# PAGE3.net
KiCad netlist of a schematic drawn in Altium Designer
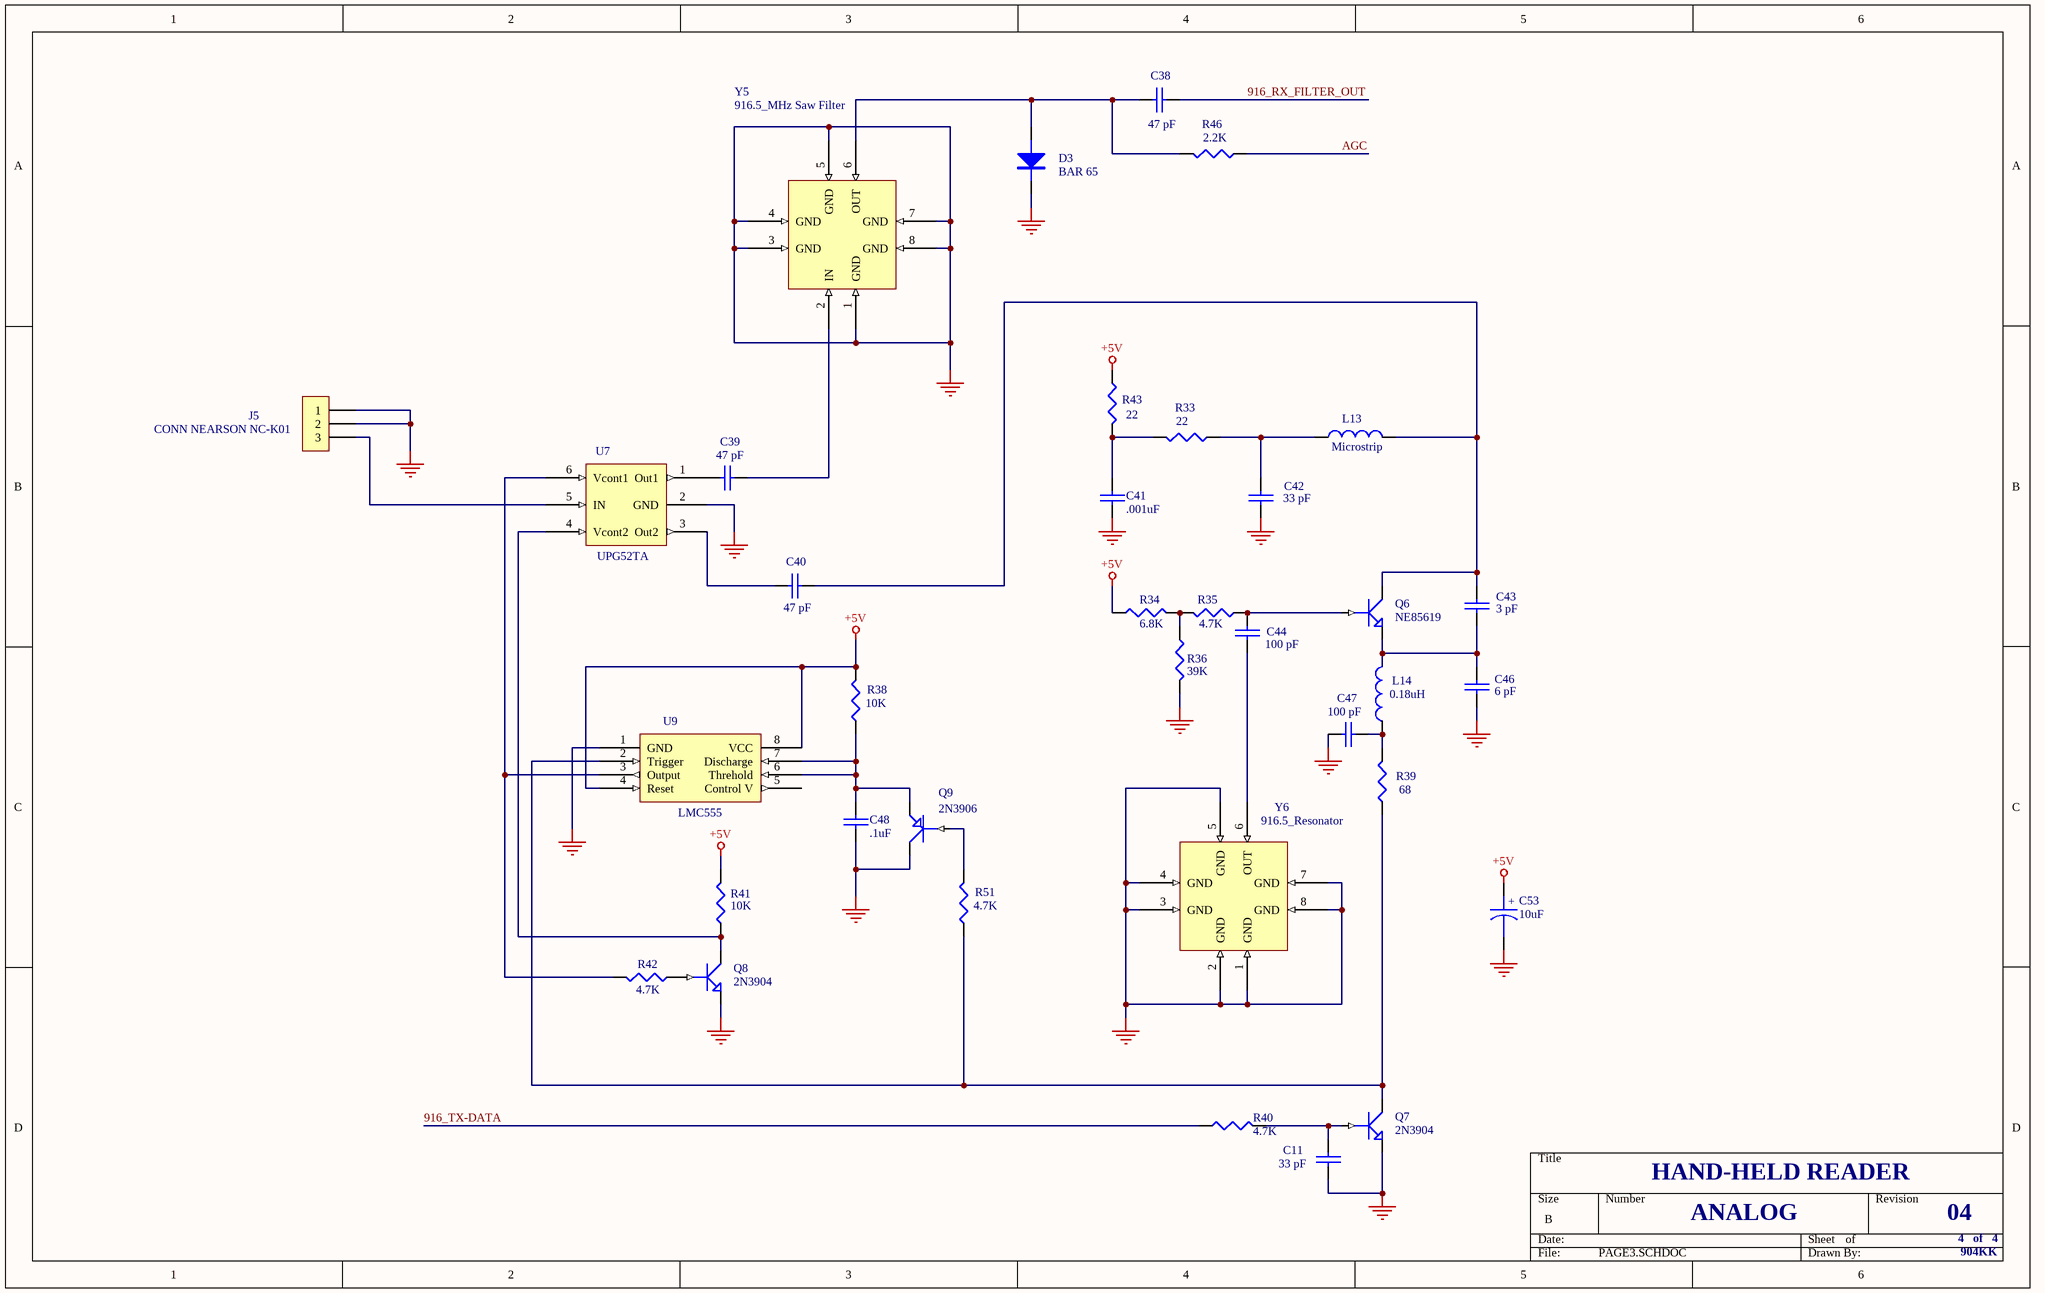
[diagram p0: PAGE3.SCHDOC]

(export (version "E")
  (design (tool "Eeschema 10.0.6"))
  (components
    (comp (ref "C11")
      (value "33 pF")
      (footprint "0603")
      (description "Capacitor")
      (libsource (lib "*") (part "CAP"))
    )
    (comp (ref "C38")
      (value "47 pF")
      (footprint "0603")
      (description "Capacitor")
      (libsource (lib "*") (part "CAP"))
    )
    (comp (ref "C39")
      (value "47 pF")
      (footprint "0603")
      (description "Capacitor")
      (libsource (lib "*") (part "CAP"))
    )
    (comp (ref "C40")
      (value "47 pF")
      (footprint "0603")
      (description "Capacitor")
      (libsource (lib "*") (part "CAP"))
    )
    (comp (ref "C41")
      (value ".001uF")
      (footprint "0603")
      (description "Capacitor")
      (libsource (lib "*") (part "CAP"))
    )
    (comp (ref "C42")
      (value "33 pF")
      (footprint "0603")
      (description "Capacitor")
      (libsource (lib "*") (part "CAP"))
    )
    (comp (ref "C43")
      (value "3 pF")
      (footprint "0603")
      (description "Capacitor")
      (libsource (lib "*") (part "CAP"))
    )
    (comp (ref "C44")
      (value "100 pF")
      (footprint "0603")
      (description "Capacitor")
      (libsource (lib "*") (part "CAP"))
    )
    (comp (ref "C46")
      (value "6 pF")
      (footprint "0603")
      (description "Capacitor")
      (libsource (lib "*") (part "CAP"))
    )
    (comp (ref "C47")
      (value "100 pF")
      (footprint "0603")
      (description "Capacitor")
      (libsource (lib "*") (part "CAP"))
    )
    (comp (ref "C48")
      (value ".1uF")
      (footprint "0603")
      (description "Capacitor")
      (libsource (lib "*") (part "CAP"))
    )
    (comp (ref "C53")
      (value "10uF")
      (footprint "CAP A CASE")
      (description "Capacitor")
      (libsource (lib "*") (part "CAPACITOR POL"))
    )
    (comp (ref "D3")
      (value "BAR 65")
      (footprint "DIODE SC79")
      (description "Diode")
      (libsource (lib "*") (part "DIODE"))
    )
    (comp (ref "J5")
      (value "CONN NEARSON NC-K01")
      (footprint "CONN NEARSON NC-K01")
      (description "Connector")
      (libsource (lib "*") (part "CON3"))
    )
    (comp (ref "L13") (value "Microstrip") (footprint "MICROSTRIP") (libsource (lib "*") (part "INDUCTOR")))
    (comp (ref "L14") (value "0.18uH") (footprint "0603") (libsource (lib "*") (part "INDUCTOR")))
    (comp (ref "Q6")
      (value "NE85619")
      (footprint "3 PIN ULTRA SUPER MINI MOLD")
      (description "NPN Transistor")
      (libsource (lib "*") (part "NPN1"))
    )
    (comp (ref "Q7")
      (value "2N3904")
      (footprint "SOT23 TRANS")
      (description "NPN Transistor")
      (libsource (lib "*") (part "NPN1"))
    )
    (comp (ref "Q8")
      (value "2N3904")
      (footprint "SOT23 TRANS")
      (description "NPN Transistor")
      (libsource (lib "*") (part "NPN1"))
    )
    (comp (ref "Q9")
      (value "2N3906")
      (footprint "SOT23 TRANS")
      (description "PNP Transistor")
      (libsource (lib "*") (part "PNP1"))
    )
    (comp (ref "R33") (value "22") (footprint "0603") (libsource (lib "*") (part "RESISTOR")))
    (comp (ref "R34") (value "6.8K") (footprint "0603") (libsource (lib "*") (part "RESISTOR")))
    (comp (ref "R35") (value "4.7K") (footprint "0603") (libsource (lib "*") (part "RESISTOR")))
    (comp (ref "R36") (value "39K") (footprint "0603") (libsource (lib "*") (part "RESISTOR")))
    (comp (ref "R38") (value "10K") (footprint "0603") (libsource (lib "*") (part "RESISTOR")))
    (comp (ref "R39") (value "68") (footprint "0603") (libsource (lib "*") (part "RESISTOR")))
    (comp (ref "R40") (value "4.7K") (footprint "0603") (libsource (lib "*") (part "RESISTOR")))
    (comp (ref "R41") (value "10K") (footprint "0603") (libsource (lib "*") (part "RESISTOR")))
    (comp (ref "R42") (value "4.7K") (footprint "0603") (libsource (lib "*") (part "RESISTOR")))
    (comp (ref "R43") (value "22") (footprint "0603") (libsource (lib "*") (part "RESISTOR")))
    (comp (ref "R46") (value "2.2K") (footprint "0603") (libsource (lib "*") (part "RESISTOR")))
    (comp (ref "R51") (value "4.7K") (footprint "0603") (libsource (lib "*") (part "RESISTOR")))
    (comp (ref "U7") (value "UPG52TA") (footprint "TO6") (libsource (lib "*") (part "UPG152TA_0")))
    (comp (ref "U9") (value "LMC555") (footprint "SO8 SMALL") (libsource (lib "*") (part "LMC555")))
    (comp (ref "Y5")
      (value "916.5_MHz Saw Filter")
      (footprint "RESONATOR")
      (libsource (lib "*") (part "SAW FILTER"))
    )
    (comp (ref "Y6")
      (value "916.5_Resonator")
      (footprint "RESONATOR")
      (libsource (lib "*") (part "RESONATOR"))
    )
  )
  (nets
    (net (code "1") (name "+5V") (class "Default")
      (node (ref "C53") (pin "1") (pinfunction "1_1") (pintype "passive"))
      (node (ref "R34") (pin "1") (pinfunction "1_1") (pintype "passive"))
      (node (ref "R38") (pin "2") (pinfunction "2_2") (pintype "passive"))
      (node (ref "R41") (pin "2") (pinfunction "2_2") (pintype "passive"))
      (node (ref "R43") (pin "1") (pinfunction "1_1") (pintype "passive"))
      (node (ref "U9") (pin "4") (pinfunction "Reset_4") (pintype "input"))
      (node (ref "U9") (pin "8") (pinfunction "VCC_8") (pintype "power_in"))
    )
    (net (code "2") (name "/916_RX_FILTER_OUT") (class "Default")
      (node (ref "C38") (pin "2") (pinfunction "2_2") (pintype "passive"))
    )
    (net (code "3") (name "/916_TX-DATA") (class "Default")
      (node (ref "R40") (pin "1") (pinfunction "1_1") (pintype "passive"))
    )
    (net (code "4") (name "/AGC") (class "Default")
      (node (ref "R46") (pin "1") (pinfunction "1_1") (pintype "passive"))
    )
    (net (code "5") (name "GND_SIGNAL") (class "Default")
      (node (ref "C11") (pin "2") (pinfunction "2_2") (pintype "passive"))
      (node (ref "C41") (pin "2") (pinfunction "2_2") (pintype "passive"))
      (node (ref "C42") (pin "2") (pinfunction "2_2") (pintype "passive"))
      (node (ref "C46") (pin "2") (pinfunction "2_2") (pintype "passive"))
      (node (ref "C47") (pin "1") (pinfunction "1_1") (pintype "passive"))
      (node (ref "C48") (pin "2") (pinfunction "2_2") (pintype "passive"))
      (node (ref "C53") (pin "2") (pinfunction "2_2") (pintype "passive"))
      (node (ref "D3") (pin "K") (pinfunction "K_K") (pintype "passive"))
      (node (ref "J5") (pin "1") (pinfunction "1_1") (pintype "passive"))
      (node (ref "J5") (pin "2") (pinfunction "2_2") (pintype "passive"))
      (node (ref "Q7") (pin "E") (pinfunction "E_E") (pintype "passive"))
      (node (ref "Q8") (pin "E") (pinfunction "E_E") (pintype "passive"))
      (node (ref "Q9") (pin "C") (pinfunction "C_C") (pintype "passive"))
      (node (ref "R36") (pin "2") (pinfunction "2_2") (pintype "passive"))
      (node (ref "U7") (pin "2") (pinfunction "GND_2") (pintype "power_in"))
      (node (ref "U9") (pin "1") (pinfunction "GND_1") (pintype "power_in"))
      (node (ref "Y5") (pin "1") (pinfunction "GND_1") (pintype "input"))
      (node (ref "Y5") (pin "3") (pinfunction "GND_3") (pintype "input"))
      (node (ref "Y5") (pin "4") (pinfunction "GND_4") (pintype "input"))
      (node (ref "Y5") (pin "5") (pinfunction "GND_5") (pintype "input"))
      (node (ref "Y5") (pin "7") (pinfunction "GND_7") (pintype "input"))
      (node (ref "Y5") (pin "8") (pinfunction "GND_8") (pintype "input"))
      (node (ref "Y6") (pin "1") (pinfunction "GND_1") (pintype "input"))
      (node (ref "Y6") (pin "2") (pinfunction "GND_2") (pintype "input"))
      (node (ref "Y6") (pin "3") (pinfunction "GND_3") (pintype "input"))
      (node (ref "Y6") (pin "4") (pinfunction "GND_4") (pintype "input"))
      (node (ref "Y6") (pin "5") (pinfunction "GND_5") (pintype "input"))
      (node (ref "Y6") (pin "7") (pinfunction "GND_7") (pintype "input"))
      (node (ref "Y6") (pin "8") (pinfunction "GND_8") (pintype "input"))
    )
    (net (code "6") (name "Net-(C11-Pad1)") (class "Default")
      (node (ref "C11") (pin "1") (pinfunction "1_1") (pintype "passive"))
      (node (ref "Q7") (pin "B") (pinfunction "B_B") (pintype "input"))
      (node (ref "R40") (pin "2") (pinfunction "2_2") (pintype "passive"))
    )
    (net (code "7") (name "Net-(C40-Pad2)") (class "Default")
      (node (ref "C40") (pin "2") (pinfunction "2_2") (pintype "passive"))
      (node (ref "C43") (pin "1") (pinfunction "1_1") (pintype "passive"))
      (node (ref "L13") (pin "2") (pinfunction "2_2") (pintype "passive"))
      (node (ref "Q6") (pin "C") (pinfunction "C_C") (pintype "passive"))
    )
    (net (code "8") (name "Net-(C41-Pad1)") (class "Default")
      (node (ref "C41") (pin "1") (pinfunction "1_1") (pintype "passive"))
      (node (ref "R33") (pin "2") (pinfunction "2_2") (pintype "passive"))
      (node (ref "R43") (pin "2") (pinfunction "2_2") (pintype "passive"))
    )
    (net (code "9") (name "Net-(C42-Pad1)") (class "Default")
      (node (ref "C42") (pin "1") (pinfunction "1_1") (pintype "passive"))
      (node (ref "L13") (pin "1") (pinfunction "1_1") (pintype "passive"))
      (node (ref "R33") (pin "1") (pinfunction "1_1") (pintype "passive"))
    )
    (net (code "10") (name "Net-(C43-Pad2)") (class "Default")
      (node (ref "C43") (pin "2") (pinfunction "2_2") (pintype "passive"))
      (node (ref "C46") (pin "1") (pinfunction "1_1") (pintype "passive"))
      (node (ref "L14") (pin "2") (pinfunction "2_2") (pintype "passive"))
      (node (ref "Q6") (pin "E") (pinfunction "E_E") (pintype "passive"))
    )
    (net (code "11") (name "Net-(C44-Pad1)") (class "Default")
      (node (ref "C44") (pin "1") (pinfunction "1_1") (pintype "passive"))
      (node (ref "Q6") (pin "B") (pinfunction "B_B") (pintype "input"))
      (node (ref "R35") (pin "1") (pinfunction "1_1") (pintype "passive"))
    )
    (net (code "12") (name "Net-(C47-Pad2)") (class "Default")
      (node (ref "C47") (pin "2") (pinfunction "2_2") (pintype "passive"))
      (node (ref "L14") (pin "1") (pinfunction "1_1") (pintype "passive"))
      (node (ref "R39") (pin "2") (pinfunction "2_2") (pintype "passive"))
    )
    (net (code "13") (name "Net-(Q8-PadB)") (class "Default")
      (node (ref "Q8") (pin "B") (pinfunction "B_B") (pintype "input"))
      (node (ref "R42") (pin "1") (pinfunction "1_1") (pintype "passive"))
    )
    (net (code "14") (name "Net-(Q9-PadB)") (class "Default")
      (node (ref "Q9") (pin "B") (pinfunction "B_B") (pintype "input"))
      (node (ref "R51") (pin "2") (pinfunction "2_2") (pintype "passive"))
    )
    (net (code "15") (name "Net-(R34-Pad2)") (class "Default")
      (node (ref "R34") (pin "2") (pinfunction "2_2") (pintype "passive"))
      (node (ref "R35") (pin "2") (pinfunction "2_2") (pintype "passive"))
      (node (ref "R36") (pin "1") (pinfunction "1_1") (pintype "passive"))
    )
    (net (code "16") (name "Net-(U7-IN)") (class "Default")
      (node (ref "J5") (pin "3") (pinfunction "3_3") (pintype "passive"))
      (node (ref "U7") (pin "5") (pinfunction "IN_5") (pintype "input"))
    )
    (net (code "17") (name "Net-(U7-Out1)") (class "Default")
      (node (ref "C39") (pin "1") (pinfunction "1_1") (pintype "passive"))
      (node (ref "U7") (pin "1") (pinfunction "Out1_1") (pintype "output"))
    )
    (net (code "18") (name "Net-(U7-Out2)") (class "Default")
      (node (ref "C40") (pin "1") (pinfunction "1_1") (pintype "passive"))
      (node (ref "U7") (pin "3") (pinfunction "Out2_3") (pintype "output"))
    )
    (net (code "19") (name "Net-(U7-Vcont1)") (class "Default")
      (node (ref "R42") (pin "2") (pinfunction "2_2") (pintype "passive"))
      (node (ref "U7") (pin "6") (pinfunction "Vcont1_6") (pintype "input"))
      (node (ref "U9") (pin "3") (pinfunction "Output_3") (pintype "output"))
    )
    (net (code "20") (name "Net-(U7-Vcont2)") (class "Default")
      (node (ref "Q8") (pin "C") (pinfunction "C_C") (pintype "passive"))
      (node (ref "R41") (pin "1") (pinfunction "1_1") (pintype "passive"))
      (node (ref "U7") (pin "4") (pinfunction "Vcont2_4") (pintype "input"))
    )
    (net (code "21") (name "Net-(U9-Discharge)") (class "Default")
      (node (ref "C48") (pin "1") (pinfunction "1_1") (pintype "passive"))
      (node (ref "Q9") (pin "E") (pinfunction "E_E") (pintype "passive"))
      (node (ref "R38") (pin "1") (pinfunction "1_1") (pintype "passive"))
      (node (ref "U9") (pin "6") (pinfunction "Threhold_6") (pintype "input"))
      (node (ref "U9") (pin "7") (pinfunction "Discharge_7") (pintype "input"))
    )
    (net (code "22") (name "Net-(U9-Trigger)") (class "Default")
      (node (ref "Q7") (pin "C") (pinfunction "C_C") (pintype "passive"))
      (node (ref "R39") (pin "1") (pinfunction "1_1") (pintype "passive"))
      (node (ref "R51") (pin "1") (pinfunction "1_1") (pintype "passive"))
      (node (ref "U9") (pin "2") (pinfunction "Trigger_2") (pintype "input"))
    )
    (net (code "23") (name "Net-(Y5-IN)") (class "Default")
      (node (ref "C39") (pin "2") (pinfunction "2_2") (pintype "passive"))
      (node (ref "Y5") (pin "2") (pinfunction "IN_2") (pintype "input"))
    )
    (net (code "24") (name "Net-(Y5-OUT)") (class "Default")
      (node (ref "C38") (pin "1") (pinfunction "1_1") (pintype "passive"))
      (node (ref "D3") (pin "A") (pinfunction "A_A") (pintype "passive"))
      (node (ref "R46") (pin "2") (pinfunction "2_2") (pintype "passive"))
      (node (ref "Y5") (pin "6") (pinfunction "OUT_6") (pintype "input"))
    )
    (net (code "25") (name "Net-(Y6-OUT)") (class "Default")
      (node (ref "C44") (pin "2") (pinfunction "2_2") (pintype "passive"))
      (node (ref "Y6") (pin "6") (pinfunction "OUT_6") (pintype "input"))
    )
    (net (code "26") (name "unconnected-(U9-Control_V-Pad5)") (class "Default")
      (node (ref "U9") (pin "5") (pinfunction "Control_V_5") (pintype "output"))
    )
  )
)
